# fpga-ground-outside.net
KiCad netlist of a schematic drawn in Altium Designer
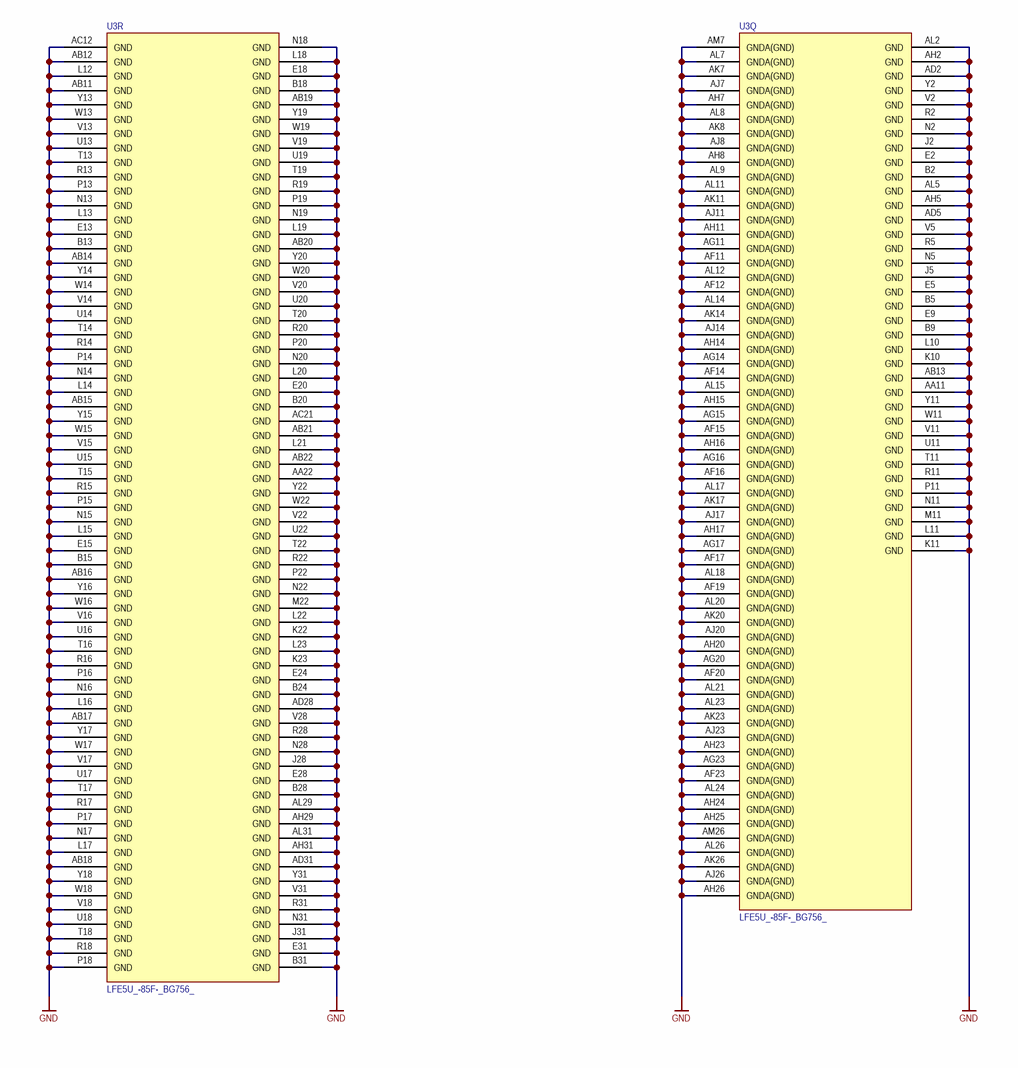
[diagram p0: fpga-ground-outside.SchDoc]

(export (version "E")
  (design (tool "Eeschema 10.0.6"))
  (components
    (comp (ref "U3")
      (value "LFE5U_-85F-_BG756_")
      (footprint "lattice:caBGA756")
      (description "ECP5 FPGA, 85k LUT, 756-caBGA")
      (fields (field (name "MANUFACTURER") "Lattice Semiconductor"))
      (libsource (lib "lattice") (part "LFE5U_-85F-_BG756_"))
    )
  )
  (nets
    (net (code "1") (name "GND") (class "Default")
      (node (ref "U3") (pin "AA11") (pinfunction "GND_AA11") (pintype "power_in"))
      (node (ref "U3") (pin "AA22") (pinfunction "GND_AA22") (pintype "power_in"))
      (node (ref "U3") (pin "AB11") (pinfunction "GND_AB11") (pintype "power_in"))
      (node (ref "U3") (pin "AB12") (pinfunction "GND_AB12") (pintype "power_in"))
      (node (ref "U3") (pin "AB13") (pinfunction "GND_AB13") (pintype "power_in"))
      (node (ref "U3") (pin "AB14") (pinfunction "GND_AB14") (pintype "power_in"))
      (node (ref "U3") (pin "AB15") (pinfunction "GND_AB15") (pintype "power_in"))
      (node (ref "U3") (pin "AB16") (pinfunction "GND_AB16") (pintype "power_in"))
      (node (ref "U3") (pin "AB17") (pinfunction "GND_AB17") (pintype "power_in"))
      (node (ref "U3") (pin "AB18") (pinfunction "GND_AB18") (pintype "power_in"))
      (node (ref "U3") (pin "AB19") (pinfunction "GND_AB19") (pintype "power_in"))
      (node (ref "U3") (pin "AB20") (pinfunction "GND_AB20") (pintype "power_in"))
      (node (ref "U3") (pin "AB21") (pinfunction "GND_AB21") (pintype "power_in"))
      (node (ref "U3") (pin "AB22") (pinfunction "GND_AB22") (pintype "power_in"))
      (node (ref "U3") (pin "AC12") (pinfunction "GND_AC12") (pintype "power_in"))
      (node (ref "U3") (pin "AC21") (pinfunction "GND_AC21") (pintype "power_in"))
      (node (ref "U3") (pin "AD2") (pinfunction "GND_AD2") (pintype "power_in"))
      (node (ref "U3") (pin "AD28") (pinfunction "GND_AD28") (pintype "power_in"))
      (node (ref "U3") (pin "AD31") (pinfunction "GND_AD31") (pintype "power_in"))
      (node (ref "U3") (pin "AD5") (pinfunction "GND_AD5") (pintype "power_in"))
      (node (ref "U3") (pin "AF11") (pinfunction "GNDA(GND)_AF11") (pintype "power_in"))
      (node (ref "U3") (pin "AF12") (pinfunction "GNDA(GND)_AF12") (pintype "power_in"))
      (node (ref "U3") (pin "AF14") (pinfunction "GNDA(GND)_AF14") (pintype "power_in"))
      (node (ref "U3") (pin "AF15") (pinfunction "GNDA(GND)_AF15") (pintype "power_in"))
      (node (ref "U3") (pin "AF16") (pinfunction "GNDA(GND)_AF16") (pintype "power_in"))
      (node (ref "U3") (pin "AF17") (pinfunction "GNDA(GND)_AF17") (pintype "power_in"))
      (node (ref "U3") (pin "AF19") (pinfunction "GNDA(GND)_AF19") (pintype "power_in"))
      (node (ref "U3") (pin "AF20") (pinfunction "GNDA(GND)_AF20") (pintype "power_in"))
      (node (ref "U3") (pin "AF23") (pinfunction "GNDA(GND)_AF23") (pintype "power_in"))
      (node (ref "U3") (pin "AG11") (pinfunction "GNDA(GND)_AG11") (pintype "power_in"))
      (node (ref "U3") (pin "AG14") (pinfunction "GNDA(GND)_AG14") (pintype "power_in"))
      (node (ref "U3") (pin "AG15") (pinfunction "GNDA(GND)_AG15") (pintype "power_in"))
      (node (ref "U3") (pin "AG16") (pinfunction "GNDA(GND)_AG16") (pintype "power_in"))
      (node (ref "U3") (pin "AG17") (pinfunction "GNDA(GND)_AG17") (pintype "power_in"))
      (node (ref "U3") (pin "AG20") (pinfunction "GNDA(GND)_AG20") (pintype "power_in"))
      (node (ref "U3") (pin "AG23") (pinfunction "GNDA(GND)_AG23") (pintype "power_in"))
      (node (ref "U3") (pin "AH11") (pinfunction "GNDA(GND)_AH11") (pintype "power_in"))
      (node (ref "U3") (pin "AH14") (pinfunction "GNDA(GND)_AH14") (pintype "power_in"))
      (node (ref "U3") (pin "AH15") (pinfunction "GNDA(GND)_AH15") (pintype "power_in"))
      (node (ref "U3") (pin "AH16") (pinfunction "GNDA(GND)_AH16") (pintype "power_in"))
      (node (ref "U3") (pin "AH17") (pinfunction "GNDA(GND)_AH17") (pintype "power_in"))
      (node (ref "U3") (pin "AH2") (pinfunction "GND_AH2") (pintype "power_in"))
      (node (ref "U3") (pin "AH20") (pinfunction "GNDA(GND)_AH20") (pintype "power_in"))
      (node (ref "U3") (pin "AH23") (pinfunction "GNDA(GND)_AH23") (pintype "power_in"))
      (node (ref "U3") (pin "AH24") (pinfunction "GNDA(GND)_AH24") (pintype "power_in"))
      (node (ref "U3") (pin "AH25") (pinfunction "GNDA(GND)_AH25") (pintype "power_in"))
      (node (ref "U3") (pin "AH26") (pinfunction "GNDA(GND)_AH26") (pintype "power_in"))
      (node (ref "U3") (pin "AH29") (pinfunction "GND_AH29") (pintype "power_in"))
      (node (ref "U3") (pin "AH31") (pinfunction "GND_AH31") (pintype "power_in"))
      (node (ref "U3") (pin "AH5") (pinfunction "GND_AH5") (pintype "power_in"))
      (node (ref "U3") (pin "AH7") (pinfunction "GNDA(GND)_AH7") (pintype "power_in"))
      (node (ref "U3") (pin "AH8") (pinfunction "GNDA(GND)_AH8") (pintype "power_in"))
      (node (ref "U3") (pin "AJ11") (pinfunction "GNDA(GND)_AJ11") (pintype "power_in"))
      (node (ref "U3") (pin "AJ14") (pinfunction "GNDA(GND)_AJ14") (pintype "power_in"))
      (node (ref "U3") (pin "AJ17") (pinfunction "GNDA(GND)_AJ17") (pintype "power_in"))
      (node (ref "U3") (pin "AJ20") (pinfunction "GNDA(GND)_AJ20") (pintype "power_in"))
      (node (ref "U3") (pin "AJ23") (pinfunction "GNDA(GND)_AJ23") (pintype "power_in"))
      (node (ref "U3") (pin "AJ26") (pinfunction "GNDA(GND)_AJ26") (pintype "power_in"))
      (node (ref "U3") (pin "AJ7") (pinfunction "GNDA(GND)_AJ7") (pintype "power_in"))
      (node (ref "U3") (pin "AJ8") (pinfunction "GNDA(GND)_AJ8") (pintype "power_in"))
      (node (ref "U3") (pin "AK11") (pinfunction "GNDA(GND)_AK11") (pintype "power_in"))
      (node (ref "U3") (pin "AK14") (pinfunction "GNDA(GND)_AK14") (pintype "power_in"))
      (node (ref "U3") (pin "AK17") (pinfunction "GNDA(GND)_AK17") (pintype "power_in"))
      (node (ref "U3") (pin "AK20") (pinfunction "GNDA(GND)_AK20") (pintype "power_in"))
      (node (ref "U3") (pin "AK23") (pinfunction "GNDA(GND)_AK23") (pintype "power_in"))
      (node (ref "U3") (pin "AK26") (pinfunction "GNDA(GND)_AK26") (pintype "power_in"))
      (node (ref "U3") (pin "AK7") (pinfunction "GNDA(GND)_AK7") (pintype "power_in"))
      (node (ref "U3") (pin "AK8") (pinfunction "GNDA(GND)_AK8") (pintype "power_in"))
      (node (ref "U3") (pin "AL11") (pinfunction "GNDA(GND)_AL11") (pintype "power_in"))
      (node (ref "U3") (pin "AL12") (pinfunction "GNDA(GND)_AL12") (pintype "power_in"))
      (node (ref "U3") (pin "AL14") (pinfunction "GNDA(GND)_AL14") (pintype "power_in"))
      (node (ref "U3") (pin "AL15") (pinfunction "GNDA(GND)_AL15") (pintype "power_in"))
      (node (ref "U3") (pin "AL17") (pinfunction "GNDA(GND)_AL17") (pintype "power_in"))
      (node (ref "U3") (pin "AL18") (pinfunction "GNDA(GND)_AL18") (pintype "power_in"))
      (node (ref "U3") (pin "AL2") (pinfunction "GND_AL2") (pintype "power_in"))
      (node (ref "U3") (pin "AL20") (pinfunction "GNDA(GND)_AL20") (pintype "power_in"))
      (node (ref "U3") (pin "AL21") (pinfunction "GNDA(GND)_AL21") (pintype "power_in"))
      (node (ref "U3") (pin "AL23") (pinfunction "GNDA(GND)_AL23") (pintype "power_in"))
      (node (ref "U3") (pin "AL24") (pinfunction "GNDA(GND)_AL24") (pintype "power_in"))
      (node (ref "U3") (pin "AL26") (pinfunction "GNDA(GND)_AL26") (pintype "power_in"))
      (node (ref "U3") (pin "AL29") (pinfunction "GND_AL29") (pintype "power_in"))
      (node (ref "U3") (pin "AL31") (pinfunction "GND_AL31") (pintype "power_in"))
      (node (ref "U3") (pin "AL5") (pinfunction "GND_AL5") (pintype "power_in"))
      (node (ref "U3") (pin "AL7") (pinfunction "GNDA(GND)_AL7") (pintype "power_in"))
      (node (ref "U3") (pin "AL8") (pinfunction "GNDA(GND)_AL8") (pintype "power_in"))
      (node (ref "U3") (pin "AL9") (pinfunction "GNDA(GND)_AL9") (pintype "power_in"))
      (node (ref "U3") (pin "AM26") (pinfunction "GNDA(GND)_AM26") (pintype "power_in"))
      (node (ref "U3") (pin "AM7") (pinfunction "GNDA(GND)_AM7") (pintype "power_in"))
      (node (ref "U3") (pin "B13") (pinfunction "GND_B13") (pintype "power_in"))
      (node (ref "U3") (pin "B15") (pinfunction "GND_B15") (pintype "power_in"))
      (node (ref "U3") (pin "B18") (pinfunction "GND_B18") (pintype "power_in"))
      (node (ref "U3") (pin "B2") (pinfunction "GND_B2") (pintype "power_in"))
      (node (ref "U3") (pin "B20") (pinfunction "GND_B20") (pintype "power_in"))
      (node (ref "U3") (pin "B24") (pinfunction "GND_B24") (pintype "power_in"))
      (node (ref "U3") (pin "B28") (pinfunction "GND_B28") (pintype "power_in"))
      (node (ref "U3") (pin "B31") (pinfunction "GND_B31") (pintype "power_in"))
      (node (ref "U3") (pin "B5") (pinfunction "GND_B5") (pintype "power_in"))
      (node (ref "U3") (pin "B9") (pinfunction "GND_B9") (pintype "power_in"))
      (node (ref "U3") (pin "E13") (pinfunction "GND_E13") (pintype "power_in"))
      (node (ref "U3") (pin "E15") (pinfunction "GND_E15") (pintype "power_in"))
      (node (ref "U3") (pin "E18") (pinfunction "GND_E18") (pintype "power_in"))
      (node (ref "U3") (pin "E2") (pinfunction "GND_E2") (pintype "power_in"))
      (node (ref "U3") (pin "E20") (pinfunction "GND_E20") (pintype "power_in"))
      (node (ref "U3") (pin "E24") (pinfunction "GND_E24") (pintype "power_in"))
      (node (ref "U3") (pin "E28") (pinfunction "GND_E28") (pintype "power_in"))
      (node (ref "U3") (pin "E31") (pinfunction "GND_E31") (pintype "power_in"))
      (node (ref "U3") (pin "E5") (pinfunction "GND_E5") (pintype "power_in"))
      (node (ref "U3") (pin "E9") (pinfunction "GND_E9") (pintype "power_in"))
      (node (ref "U3") (pin "J2") (pinfunction "GND_J2") (pintype "power_in"))
      (node (ref "U3") (pin "J28") (pinfunction "GND_J28") (pintype "power_in"))
      (node (ref "U3") (pin "J31") (pinfunction "GND_J31") (pintype "power_in"))
      (node (ref "U3") (pin "J5") (pinfunction "GND_J5") (pintype "power_in"))
      (node (ref "U3") (pin "K10") (pinfunction "GND_K10") (pintype "power_in"))
      (node (ref "U3") (pin "K11") (pinfunction "GND_K11") (pintype "power_in"))
      (node (ref "U3") (pin "K22") (pinfunction "GND_K22") (pintype "power_in"))
      (node (ref "U3") (pin "K23") (pinfunction "GND_K23") (pintype "power_in"))
      (node (ref "U3") (pin "L10") (pinfunction "GND_L10") (pintype "power_in"))
      (node (ref "U3") (pin "L11") (pinfunction "GND_L11") (pintype "power_in"))
      (node (ref "U3") (pin "L12") (pinfunction "GND_L12") (pintype "power_in"))
      (node (ref "U3") (pin "L13") (pinfunction "GND_L13") (pintype "power_in"))
      (node (ref "U3") (pin "L14") (pinfunction "GND_L14") (pintype "power_in"))
      (node (ref "U3") (pin "L15") (pinfunction "GND_L15") (pintype "power_in"))
      (node (ref "U3") (pin "L16") (pinfunction "GND_L16") (pintype "power_in"))
      (node (ref "U3") (pin "L17") (pinfunction "GND_L17") (pintype "power_in"))
      (node (ref "U3") (pin "L18") (pinfunction "GND_L18") (pintype "power_in"))
      (node (ref "U3") (pin "L19") (pinfunction "GND_L19") (pintype "power_in"))
      (node (ref "U3") (pin "L20") (pinfunction "GND_L20") (pintype "power_in"))
      (node (ref "U3") (pin "L21") (pinfunction "GND_L21") (pintype "power_in"))
      (node (ref "U3") (pin "L22") (pinfunction "GND_L22") (pintype "power_in"))
      (node (ref "U3") (pin "L23") (pinfunction "GND_L23") (pintype "power_in"))
      (node (ref "U3") (pin "M11") (pinfunction "GND_M11") (pintype "power_in"))
      (node (ref "U3") (pin "M22") (pinfunction "GND_M22") (pintype "power_in"))
      (node (ref "U3") (pin "N11") (pinfunction "GND_N11") (pintype "power_in"))
      (node (ref "U3") (pin "N13") (pinfunction "GND_N13") (pintype "power_in"))
      (node (ref "U3") (pin "N14") (pinfunction "GND_N14") (pintype "power_in"))
      (node (ref "U3") (pin "N15") (pinfunction "GND_N15") (pintype "power_in"))
      (node (ref "U3") (pin "N16") (pinfunction "GND_N16") (pintype "power_in"))
      (node (ref "U3") (pin "N17") (pinfunction "GND_N17") (pintype "power_in"))
      (node (ref "U3") (pin "N18") (pinfunction "GND_N18") (pintype "power_in"))
      (node (ref "U3") (pin "N19") (pinfunction "GND_N19") (pintype "power_in"))
      (node (ref "U3") (pin "N2") (pinfunction "GND_N2") (pintype "power_in"))
      (node (ref "U3") (pin "N20") (pinfunction "GND_N20") (pintype "power_in"))
      (node (ref "U3") (pin "N22") (pinfunction "GND_N22") (pintype "power_in"))
      (node (ref "U3") (pin "N28") (pinfunction "GND_N28") (pintype "power_in"))
      (node (ref "U3") (pin "N31") (pinfunction "GND_N31") (pintype "power_in"))
      (node (ref "U3") (pin "N5") (pinfunction "GND_N5") (pintype "power_in"))
      (node (ref "U3") (pin "P11") (pinfunction "GND_P11") (pintype "power_in"))
      (node (ref "U3") (pin "P13") (pinfunction "GND_P13") (pintype "power_in"))
      (node (ref "U3") (pin "P14") (pinfunction "GND_P14") (pintype "power_in"))
      (node (ref "U3") (pin "P15") (pinfunction "GND_P15") (pintype "power_in"))
      (node (ref "U3") (pin "P16") (pinfunction "GND_P16") (pintype "power_in"))
      (node (ref "U3") (pin "P17") (pinfunction "GND_P17") (pintype "power_in"))
      (node (ref "U3") (pin "P18") (pinfunction "GND_P18") (pintype "power_in"))
      (node (ref "U3") (pin "P19") (pinfunction "GND_P19") (pintype "power_in"))
      (node (ref "U3") (pin "P20") (pinfunction "GND_P20") (pintype "power_in"))
      (node (ref "U3") (pin "P22") (pinfunction "GND_P22") (pintype "power_in"))
      (node (ref "U3") (pin "R11") (pinfunction "GND_R11") (pintype "power_in"))
      (node (ref "U3") (pin "R13") (pinfunction "GND_R13") (pintype "power_in"))
      (node (ref "U3") (pin "R14") (pinfunction "GND_R14") (pintype "power_in"))
      (node (ref "U3") (pin "R15") (pinfunction "GND_R15") (pintype "power_in"))
      (node (ref "U3") (pin "R16") (pinfunction "GND_R16") (pintype "power_in"))
      (node (ref "U3") (pin "R17") (pinfunction "GND_R17") (pintype "power_in"))
      (node (ref "U3") (pin "R18") (pinfunction "GND_R18") (pintype "power_in"))
      (node (ref "U3") (pin "R19") (pinfunction "GND_R19") (pintype "power_in"))
      (node (ref "U3") (pin "R2") (pinfunction "GND_R2") (pintype "power_in"))
      (node (ref "U3") (pin "R20") (pinfunction "GND_R20") (pintype "power_in"))
      (node (ref "U3") (pin "R22") (pinfunction "GND_R22") (pintype "power_in"))
      (node (ref "U3") (pin "R28") (pinfunction "GND_R28") (pintype "power_in"))
      (node (ref "U3") (pin "R31") (pinfunction "GND_R31") (pintype "power_in"))
      (node (ref "U3") (pin "R5") (pinfunction "GND_R5") (pintype "power_in"))
      (node (ref "U3") (pin "T11") (pinfunction "GND_T11") (pintype "power_in"))
      (node (ref "U3") (pin "T13") (pinfunction "GND_T13") (pintype "power_in"))
      (node (ref "U3") (pin "T14") (pinfunction "GND_T14") (pintype "power_in"))
      (node (ref "U3") (pin "T15") (pinfunction "GND_T15") (pintype "power_in"))
      (node (ref "U3") (pin "T16") (pinfunction "GND_T16") (pintype "power_in"))
      (node (ref "U3") (pin "T17") (pinfunction "GND_T17") (pintype "power_in"))
      (node (ref "U3") (pin "T18") (pinfunction "GND_T18") (pintype "power_in"))
      (node (ref "U3") (pin "T19") (pinfunction "GND_T19") (pintype "power_in"))
      (node (ref "U3") (pin "T20") (pinfunction "GND_T20") (pintype "power_in"))
      (node (ref "U3") (pin "T22") (pinfunction "GND_T22") (pintype "power_in"))
      (node (ref "U3") (pin "U11") (pinfunction "GND_U11") (pintype "power_in"))
      (node (ref "U3") (pin "U13") (pinfunction "GND_U13") (pintype "power_in"))
      (node (ref "U3") (pin "U14") (pinfunction "GND_U14") (pintype "power_in"))
      (node (ref "U3") (pin "U15") (pinfunction "GND_U15") (pintype "power_in"))
      (node (ref "U3") (pin "U16") (pinfunction "GND_U16") (pintype "power_in"))
      (node (ref "U3") (pin "U17") (pinfunction "GND_U17") (pintype "power_in"))
      (node (ref "U3") (pin "U18") (pinfunction "GND_U18") (pintype "power_in"))
      (node (ref "U3") (pin "U19") (pinfunction "GND_U19") (pintype "power_in"))
      (node (ref "U3") (pin "U20") (pinfunction "GND_U20") (pintype "power_in"))
      (node (ref "U3") (pin "U22") (pinfunction "GND_U22") (pintype "power_in"))
      (node (ref "U3") (pin "V11") (pinfunction "GND_V11") (pintype "power_in"))
      (node (ref "U3") (pin "V13") (pinfunction "GND_V13") (pintype "power_in"))
      (node (ref "U3") (pin "V14") (pinfunction "GND_V14") (pintype "power_in"))
      (node (ref "U3") (pin "V15") (pinfunction "GND_V15") (pintype "power_in"))
      (node (ref "U3") (pin "V16") (pinfunction "GND_V16") (pintype "power_in"))
      (node (ref "U3") (pin "V17") (pinfunction "GND_V17") (pintype "power_in"))
      (node (ref "U3") (pin "V18") (pinfunction "GND_V18") (pintype "power_in"))
      (node (ref "U3") (pin "V19") (pinfunction "GND_V19") (pintype "power_in"))
      (node (ref "U3") (pin "V2") (pinfunction "GND_V2") (pintype "power_in"))
      (node (ref "U3") (pin "V20") (pinfunction "GND_V20") (pintype "power_in"))
      (node (ref "U3") (pin "V22") (pinfunction "GND_V22") (pintype "power_in"))
      (node (ref "U3") (pin "V28") (pinfunction "GND_V28") (pintype "power_in"))
      (node (ref "U3") (pin "V31") (pinfunction "GND_V31") (pintype "power_in"))
      (node (ref "U3") (pin "V5") (pinfunction "GND_V5") (pintype "power_in"))
      (node (ref "U3") (pin "W11") (pinfunction "GND_W11") (pintype "power_in"))
      (node (ref "U3") (pin "W13") (pinfunction "GND_W13") (pintype "power_in"))
      (node (ref "U3") (pin "W14") (pinfunction "GND_W14") (pintype "power_in"))
      (node (ref "U3") (pin "W15") (pinfunction "GND_W15") (pintype "power_in"))
      (node (ref "U3") (pin "W16") (pinfunction "GND_W16") (pintype "power_in"))
      (node (ref "U3") (pin "W17") (pinfunction "GND_W17") (pintype "power_in"))
      (node (ref "U3") (pin "W18") (pinfunction "GND_W18") (pintype "power_in"))
      (node (ref "U3") (pin "W19") (pinfunction "GND_W19") (pintype "power_in"))
      (node (ref "U3") (pin "W20") (pinfunction "GND_W20") (pintype "power_in"))
      (node (ref "U3") (pin "W22") (pinfunction "GND_W22") (pintype "power_in"))
      (node (ref "U3") (pin "Y11") (pinfunction "GND_Y11") (pintype "power_in"))
      (node (ref "U3") (pin "Y13") (pinfunction "GND_Y13") (pintype "power_in"))
      (node (ref "U3") (pin "Y14") (pinfunction "GND_Y14") (pintype "power_in"))
      (node (ref "U3") (pin "Y15") (pinfunction "GND_Y15") (pintype "power_in"))
      (node (ref "U3") (pin "Y16") (pinfunction "GND_Y16") (pintype "power_in"))
      (node (ref "U3") (pin "Y17") (pinfunction "GND_Y17") (pintype "power_in"))
      (node (ref "U3") (pin "Y18") (pinfunction "GND_Y18") (pintype "power_in"))
      (node (ref "U3") (pin "Y19") (pinfunction "GND_Y19") (pintype "power_in"))
      (node (ref "U3") (pin "Y2") (pinfunction "GND_Y2") (pintype "power_in"))
      (node (ref "U3") (pin "Y20") (pinfunction "GND_Y20") (pintype "power_in"))
      (node (ref "U3") (pin "Y22") (pinfunction "GND_Y22") (pintype "power_in"))
      (node (ref "U3") (pin "Y31") (pinfunction "GND_Y31") (pintype "power_in"))
    )
  )
)
